# PowerPCB.net
KiCad netlist of a schematic drawn in Altium Designer
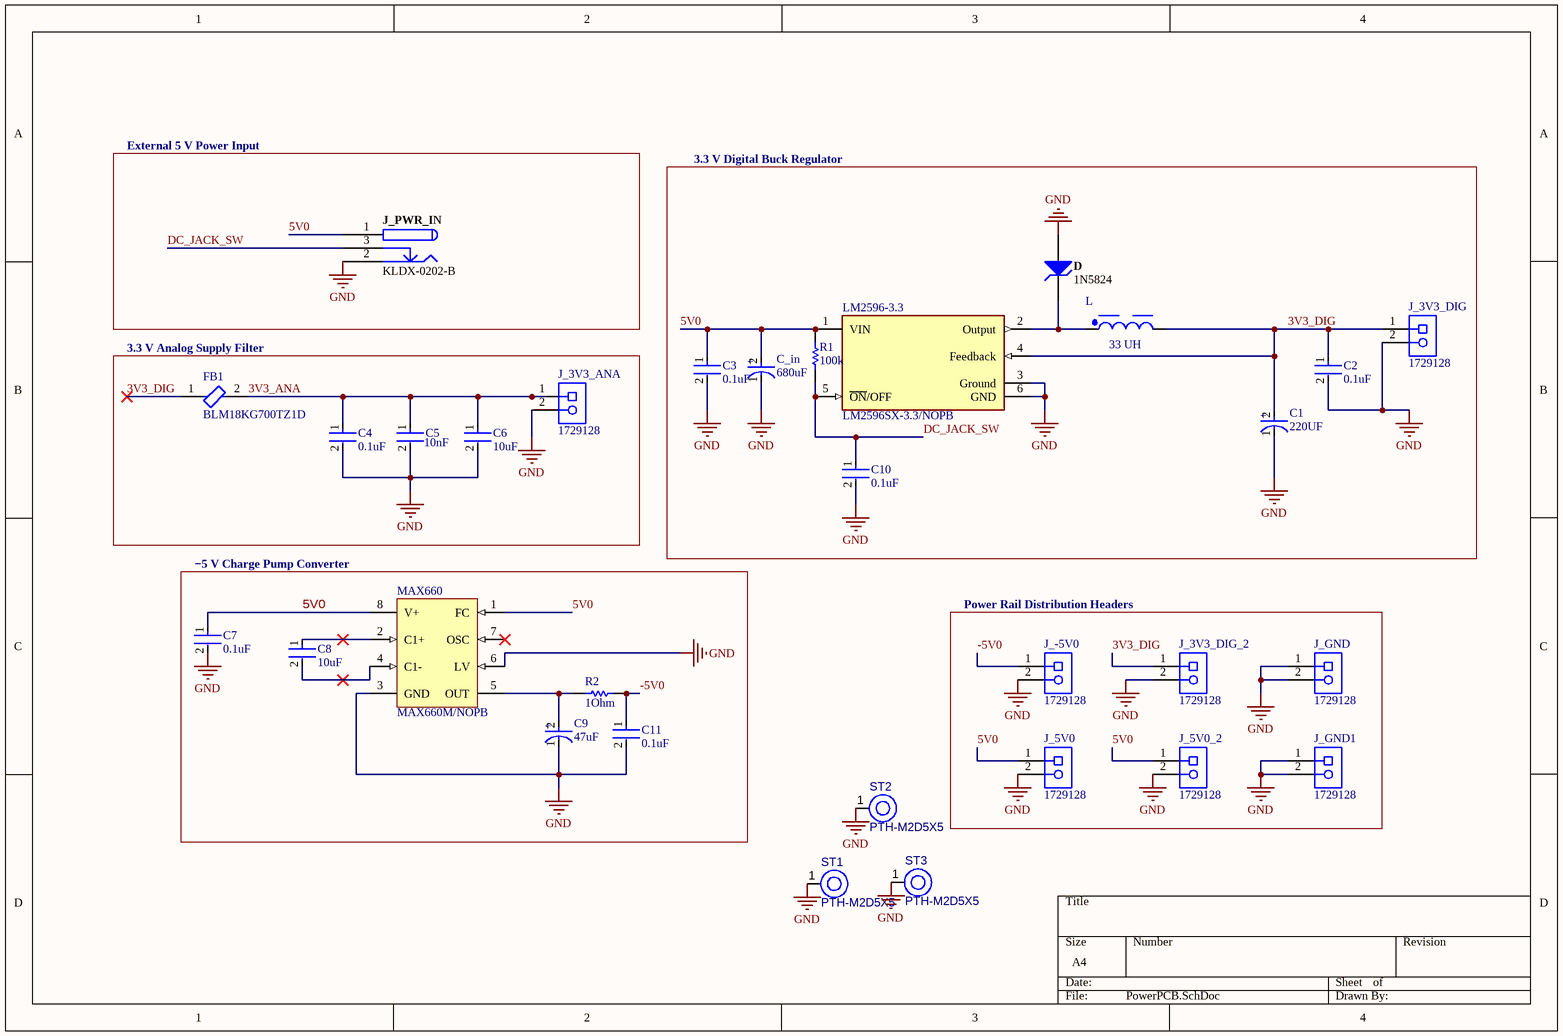
[diagram p0: PowerPCB.SchDoc]

(export (version "E")
  (design (tool "Eeschema 10.0.6"))
  (components
    (comp (ref "C1")
      (value "220UF")
      (footprint "FP-RAD-TH-D_6_3_0_5-L_11-MFG")
      (description "Aluminum Electrolytic Capacitors (Radial Lead Type) AEC-Q200 Qualified 220uF ±20% 16V")
      (fields (field (name "TOLERANCE") "20%"))
      (libsource (lib "Altium Content Vault") (part "203bc49f2ac43e59fd269a8c329ed05"))
    )
    (comp (ref "C2")
      (value "0.1uF")
      (footprint "FP-RDE0M1-MFG")
      (description "Ceramic Capacitor 100nF ±10% 25V X7R Radial")
      (fields (field (name "TOLERANCE") "10%"))
      (libsource (lib "Altium Content Vault") (part "b4654b650e69147ec39a6b967a45e02"))
    )
    (comp (ref "C3")
      (value "0.1uF")
      (footprint "FP-RDE0M1-MFG")
      (description "Ceramic Capacitor 100nF ±10% 25V X7R Radial")
      (fields (field (name "TOLERANCE") "10%"))
      (libsource (lib "Altium Content Vault") (part "b4654b650e69147ec39a6b967a45e02"))
    )
    (comp (ref "C4")
      (value "0.1uF")
      (footprint "FP-RDE0M1-MFG")
      (description "Ceramic Capacitor 100nF ±10% 25V X7R Radial")
      (fields (field (name "TOLERANCE") "10%"))
      (libsource (lib "Altium Content Vault") (part "b4654b650e69147ec39a6b967a45e02"))
    )
    (comp (ref "C5")
      (value "10nF")
      (footprint "FP-RDE0M1-MFG")
      (description "Ceramic Capacitor 10nF ±10% 100V X7R Radial")
      (fields (field (name "TOLERANCE") "10%"))
      (libsource (lib "Altium Content Vault") (part "b4654b650e69147ec39a6b967a45e02"))
    )
    (comp (ref "C6")
      (value "10uF")
      (footprint "FP-RDE2P1-MFG")
      (description "Ceramic Capacitor 10uF ±10% 25V X7S Radial")
      (fields (field (name "TOLERANCE") "10%"))
      (libsource (lib "Altium Content Vault") (part "02cd4be3c70576c341d710602a673aa"))
    )
    (comp (ref "C7")
      (value "0.1uF")
      (footprint "FP-RDE0M1-MFG")
      (description "Ceramic Capacitor 100nF ±10% 25V X7R Radial")
      (fields (field (name "TOLERANCE") "10%"))
      (libsource (lib "Altium Content Vault") (part "b4654b650e69147ec39a6b967a45e02"))
    )
    (comp (ref "C8")
      (value "10uF")
      (footprint "FP-RDE2P1-MFG")
      (description "Ceramic Capacitor 10uF ±10% 25V X7S Radial")
      (fields (field (name "TOLERANCE") "10%"))
      (libsource (lib "Altium Content Vault") (part "02cd4be3c70576c341d710602a673aa"))
    )
    (comp (ref "C9")
      (value "47uF")
      (footprint "FP-RAD-TH-D_6_3_0_5-L_11-MFG")
      (description "Aluminum Electrolytic Capacitors (Radial Lead Type) 47uF ±20% 63V")
      (fields (field (name "TOLERANCE") "20%"))
      (libsource (lib "Altium Content Vault") (part "a00bbbee19879c290e62620ae7e47b1"))
    )
    (comp (ref "C10")
      (value "0.1uF")
      (footprint "FP-RDE0M1-MFG")
      (description "Ceramic Capacitor 100nF ±10% 25V X7R Radial")
      (fields (field (name "TOLERANCE") "10%"))
      (libsource (lib "Altium Content Vault") (part "b4654b650e69147ec39a6b967a45e02"))
    )
    (comp (ref "C11")
      (value "0.1uF")
      (footprint "FP-RDE0M1-MFG")
      (description "Ceramic Capacitor 100nF ±10% 25V X7R Radial")
      (fields (field (name "TOLERANCE") "10%"))
      (libsource (lib "Altium Content Vault") (part "b4654b650e69147ec39a6b967a45e02"))
    )
    (comp (ref "C_in")
      (value "680uF")
      (footprint "FP-RAD-TH-D_10_0_5-L_25_2-MFG")
      (description "Aluminum Electrolytic Capacitors (Radial Lead Type) 680uF ±20% 35V")
      (libsource (lib "Altium Content Vault") (part "a00bbbee19879c290e62620ae7e47b1"))
    )
    (comp (ref "D")
      (value "1N5824")
      (footprint "FAIR-DO-41-2_V")
      (description "Zener Diode, 7.5V, 1W, 5%, -65 to 200 degC, 2-Pin DO-41, Body 2.72 x 5.2 mm, RoHS")
      (fields (field (name "TOLERANCE") "5%") (field (name "PARTNUMBER") "1N4737A"))
      (libsource (lib "Altium Content Vault") (part "FAIR-DZEN-A1K2-2"))
    )
    (comp (ref "FB1")
      (value "BLM18KG700TZ1D")
      (footprint "FP-BLM18-0_15-t0_6-d1_2-IPC_A")
      (description "Chip Ferrite Bead Array, 0603, 70Ω @ 100MHz, 25%, 0.022Ω, 3.5A")
      (libsource (lib "Altium Content Vault") (part "5f30dd21d616792df468990f7003faa"))
    )
    (comp (ref "J_-5V0")
      (value "1729128")
      (footprint "PHOE-1729128-2_V")
      (description "PCB Terminal Block, 13.5 A, 400 V, 2-Pin THD, RoHS, Bulk")
      (fields (field (name "MANUFACTURER") "Phoenix Contact"))
      (libsource (lib "Altium Content Vault") (part "CN-2P-F-R2"))
    )
    (comp (ref "J_3V3_ANA")
      (value "1729128")
      (footprint "PHOE-1729128-2_V")
      (description "PCB Terminal Block, 13.5 A, 400 V, 2-Pin THD, RoHS, Bulk")
      (fields (field (name "MANUFACTURER") "Phoenix Contact"))
      (libsource (lib "Altium Content Vault") (part "CN-2P-F-R2"))
    )
    (comp (ref "J_3V3_DIG")
      (value "1729128")
      (footprint "PHOE-1729128-2_V")
      (description "PCB Terminal Block, 13.5 A, 400 V, 2-Pin THD, RoHS, Bulk")
      (fields (field (name "MANUFACTURER") "Phoenix Contact"))
      (libsource (lib "Altium Content Vault") (part "CN-2P-F-R2"))
    )
    (comp (ref "J_3V3_DIG_2")
      (value "1729128")
      (footprint "PHOE-1729128-2_V")
      (description "PCB Terminal Block, 13.5 A, 400 V, 2-Pin THD, RoHS, Bulk")
      (fields (field (name "MANUFACTURER") "Phoenix Contact"))
      (libsource (lib "Altium Content Vault") (part "CN-2P-F-R2"))
    )
    (comp (ref "J_5V0")
      (value "1729128")
      (footprint "PHOE-1729128-2_V")
      (description "PCB Terminal Block, 13.5 A, 400 V, 2-Pin THD, RoHS, Bulk")
      (fields (field (name "MANUFACTURER") "Phoenix Contact"))
      (libsource (lib "Altium Content Vault") (part "CN-2P-F-R2"))
    )
    (comp (ref "J_5V0_2")
      (value "1729128")
      (footprint "PHOE-1729128-2_V")
      (description "PCB Terminal Block, 13.5 A, 400 V, 2-Pin THD, RoHS, Bulk")
      (fields (field (name "MANUFACTURER") "Phoenix Contact"))
      (libsource (lib "Altium Content Vault") (part "CN-2P-F-R2"))
    )
    (comp (ref "J_GND")
      (value "1729128")
      (footprint "PHOE-1729128-2_V")
      (description "PCB Terminal Block, 13.5 A, 400 V, 2-Pin THD, RoHS, Bulk")
      (fields (field (name "MANUFACTURER") "Phoenix Contact"))
      (libsource (lib "Altium Content Vault") (part "CN-2P-F-R2"))
    )
    (comp (ref "J_GND1")
      (value "1729128")
      (footprint "PHOE-1729128-2_V")
      (description "PCB Terminal Block, 13.5 A, 400 V, 2-Pin THD, RoHS, Bulk")
      (fields (field (name "MANUFACTURER") "Phoenix Contact"))
      (libsource (lib "Altium Content Vault") (part "CN-2P-F-R2"))
    )
    (comp (ref "J_PWR_IN")
      (value "KLDX-0202-B")
      (footprint "KYCN-KLDX-0202-B_V")
      (description "3 Conductor Power Jack, 2 break 2 aux contacts")
      (libsource (lib "Altium Content Vault") (part "KYCN-KLDX-0202-B-3"))
    )
    (comp (ref "L")
      (value "33 UH")
      (footprint "WE-TIS_1111")
      (description "Inductor Power Shielded Wirewound 33uH 20% 1KHz Ferrite 3.6A 61mOhm DCR RDL Tray")
      (fields (field (name "TOLERANCE") "20%"))
      (libsource (lib "Altium Content Vault") (part "Inductor - 2"))
    )
    (comp (ref "LM2596-3.3")
      (value "LM2596SX-3.3/NOPB")
      (footprint "FP-KTT0005B-MFG")
      (description "IC REG BUCK 3.3V 3A TO263-5")
      (libsource (lib "Altium Content Vault") (part "764e866748593119a4ee8b47c98b122"))
    )
    (comp (ref "MAX660")
      (value "MAX660M/NOPB")
      (footprint "D0008A_L")
      (description "Switched Capacitor Voltage Converter, 8-pin Narrow SOIC, Pb-Free")
      (fields (field (name "MANUFACTURER") "Texas Instruments"))
      (libsource (lib "Altium Content Vault") (part "PM-CHP-LM2660M-8"))
    )
    (comp (ref "R1")
      (value "100k")
      (footprint "RESA60-630X240")
      (description "Axial Resistor, 1 MOhm, +/- 1%, 250 mW, -55 to 155 degC, 2-Pin THD, RoHS, Bulk")
      (fields (field (name "TOLERANCE") "1%"))
      (libsource (lib "Altium Content Vault") (part "RES-2"))
    )
    (comp (ref "R2")
      (value "1Ohm")
      (footprint "RESA60-630X240")
      (description "Axial Resistor, 1 MOhm, +/- 1%, 250 mW, -55 to 155 degC, 2-Pin THD, RoHS, Bulk")
      (fields (field (name "TOLERANCE") "1%"))
      (libsource (lib "Altium Content Vault") (part "RES-2"))
    )
    (comp (ref "ST1")
      (value "PTH-M2D5X5")
      (footprint "PTH-M2D5X5")
      (description "M2 PTH (2.5mm), 5mm pad")
      (libsource (lib "ENEL 400") (part "CMP-00028-00000-1"))
    )
    (comp (ref "ST2")
      (value "PTH-M2D5X5")
      (footprint "PTH-M2D5X5")
      (description "M2 PTH (2.5mm), 5mm pad")
      (libsource (lib "ENEL 400") (part "CMP-00028-00000-1"))
    )
    (comp (ref "ST3")
      (value "PTH-M2D5X5")
      (footprint "PTH-M2D5X5")
      (description "M2 PTH (2.5mm), 5mm pad")
      (libsource (lib "ENEL 400") (part "CMP-00028-00000-1"))
    )
  )
  (nets
    (net (code "1") (name "/-5V0") (class "Default")
      (node (ref "C11") (pin "1") (pinfunction "1_1") (pintype "passive"))
      (node (ref "J_-5V0") (pin "1") (pinfunction "1_1") (pintype "passive"))
      (node (ref "R2") (pin "2") (pinfunction "2_2") (pintype "passive"))
    )
    (net (code "2") (name "/3V3_ANA") (class "Default")
      (node (ref "C4") (pin "1") (pinfunction "1_1") (pintype "passive"))
      (node (ref "C5") (pin "1") (pinfunction "1_1") (pintype "passive"))
      (node (ref "C6") (pin "1") (pinfunction "1_1") (pintype "passive"))
      (node (ref "FB1") (pin "2") (pinfunction "2_2") (pintype "passive"))
      (node (ref "J_3V3_ANA") (pin "1") (pinfunction "1_1") (pintype "passive"))
    )
    (net (code "3") (name "/3V3_DIG") (class "Default")
      (node (ref "C1") (pin "2") (pinfunction "A_2") (pintype "passive"))
      (node (ref "C2") (pin "1") (pinfunction "1_1") (pintype "passive"))
      (node (ref "FB1") (pin "1") (pinfunction "1_1") (pintype "passive"))
      (node (ref "J_3V3_DIG") (pin "1") (pinfunction "1_1") (pintype "passive"))
      (node (ref "J_3V3_DIG_2") (pin "1") (pinfunction "1_1") (pintype "passive"))
      (node (ref "L") (pin "2") (pinfunction "2_2") (pintype "passive"))
      (node (ref "LM2596-3.3") (pin "4") (pinfunction "Feedback_4") (pintype "input"))
    )
    (net (code "4") (name "/5V0") (class "Default")
      (node (ref "C3") (pin "1") (pinfunction "1_1") (pintype "passive"))
      (node (ref "C7") (pin "1") (pinfunction "1_1") (pintype "passive"))
      (node (ref "C_in") (pin "2") (pinfunction "A_2") (pintype "passive"))
      (node (ref "J_5V0") (pin "1") (pinfunction "1_1") (pintype "passive"))
      (node (ref "J_5V0_2") (pin "1") (pinfunction "1_1") (pintype "passive"))
      (node (ref "J_PWR_IN") (pin "1") (pintype "power_in"))
      (node (ref "LM2596-3.3") (pin "1") (pinfunction "VIN_1") (pintype "power_in"))
      (node (ref "MAX660") (pin "1") (pinfunction "FC_1") (pintype "input"))
      (node (ref "MAX660") (pin "8") (pinfunction "V+_8") (pintype "power_in"))
      (node (ref "R1") (pin "2") (pinfunction "2_2") (pintype "passive"))
    )
    (net (code "5") (name "/DC_JACK_SW") (class "Default")
      (node (ref "C10") (pin "1") (pinfunction "1_1") (pintype "passive"))
      (node (ref "J_PWR_IN") (pin "3") (pintype "power_in"))
      (node (ref "LM2596-3.3") (pin "5") (pinfunction "~{ON}/OFF_5") (pintype "input"))
      (node (ref "R1") (pin "1") (pinfunction "1_1") (pintype "passive"))
    )
    (net (code "6") (name "GND") (class "Default")
      (node (ref "C1") (pin "1") (pinfunction "C_1") (pintype "passive"))
      (node (ref "C10") (pin "2") (pinfunction "2_2") (pintype "passive"))
      (node (ref "C11") (pin "2") (pinfunction "2_2") (pintype "passive"))
      (node (ref "C2") (pin "2") (pinfunction "2_2") (pintype "passive"))
      (node (ref "C3") (pin "2") (pinfunction "2_2") (pintype "passive"))
      (node (ref "C4") (pin "2") (pinfunction "2_2") (pintype "passive"))
      (node (ref "C5") (pin "2") (pinfunction "2_2") (pintype "passive"))
      (node (ref "C6") (pin "2") (pinfunction "2_2") (pintype "passive"))
      (node (ref "C7") (pin "2") (pinfunction "2_2") (pintype "passive"))
      (node (ref "C9") (pin "1") (pinfunction "C_1") (pintype "passive"))
      (node (ref "C_in") (pin "1") (pinfunction "C_1") (pintype "passive"))
      (node (ref "D") (pin "1") (pinfunction "A_1") (pintype "passive"))
      (node (ref "J_-5V0") (pin "2") (pinfunction "2_2") (pintype "passive"))
      (node (ref "J_3V3_ANA") (pin "2") (pinfunction "2_2") (pintype "passive"))
      (node (ref "J_3V3_DIG") (pin "2") (pinfunction "2_2") (pintype "passive"))
      (node (ref "J_3V3_DIG_2") (pin "2") (pinfunction "2_2") (pintype "passive"))
      (node (ref "J_5V0") (pin "2") (pinfunction "2_2") (pintype "passive"))
      (node (ref "J_5V0_2") (pin "2") (pinfunction "2_2") (pintype "passive"))
      (node (ref "J_GND") (pin "1") (pinfunction "1_1") (pintype "passive"))
      (node (ref "J_GND") (pin "2") (pinfunction "2_2") (pintype "passive"))
      (node (ref "J_GND1") (pin "1") (pinfunction "1_1") (pintype "passive"))
      (node (ref "J_GND1") (pin "2") (pinfunction "2_2") (pintype "passive"))
      (node (ref "J_PWR_IN") (pin "2") (pintype "power_in"))
      (node (ref "LM2596-3.3") (pin "3") (pinfunction "Ground_3") (pintype "power_in"))
      (node (ref "LM2596-3.3") (pin "6") (pinfunction "GND_6") (pintype "power_in"))
      (node (ref "MAX660") (pin "3") (pinfunction "GND_3") (pintype "power_in"))
      (node (ref "MAX660") (pin "6") (pinfunction "LV_6") (pintype "input"))
      (node (ref "ST1") (pin "1") (pinfunction "H1_1") (pintype "passive"))
      (node (ref "ST2") (pin "1") (pinfunction "H1_1") (pintype "passive"))
      (node (ref "ST3") (pin "1") (pinfunction "H1_1") (pintype "passive"))
    )
    (net (code "7") (name "Net-(C9-A)") (class "Default")
      (node (ref "C9") (pin "2") (pinfunction "A_2") (pintype "passive"))
      (node (ref "MAX660") (pin "5") (pinfunction "OUT_5") (pintype "power_in"))
      (node (ref "R2") (pin "1") (pinfunction "1_1") (pintype "passive"))
    )
    (net (code "8") (name "Net-(D-K)") (class "Default")
      (node (ref "D") (pin "2") (pinfunction "K_2") (pintype "passive"))
      (node (ref "L") (pin "1") (pinfunction "1_1") (pintype "passive"))
      (node (ref "LM2596-3.3") (pin "2") (pinfunction "Output_2") (pintype "output"))
    )
    (net (code "9") (name "Net-(MAX660-C1+)") (class "Default")
      (node (ref "C8") (pin "1") (pinfunction "1_1") (pintype "passive"))
      (node (ref "MAX660") (pin "2") (pinfunction "C1+_2") (pintype "input"))
    )
    (net (code "10") (name "Net-(MAX660-C1-)") (class "Default")
      (node (ref "C8") (pin "2") (pinfunction "2_2") (pintype "passive"))
      (node (ref "MAX660") (pin "4") (pinfunction "C1-_4") (pintype "input"))
    )
    (net (code "11") (name "unconnected-(MAX660-OSC-Pad7)") (class "Default")
      (node (ref "MAX660") (pin "7") (pinfunction "OSC_7") (pintype "input+no_connect"))
    )
  )
)
